# SCH.net
KiCad netlist of a schematic drawn in Altium Designer
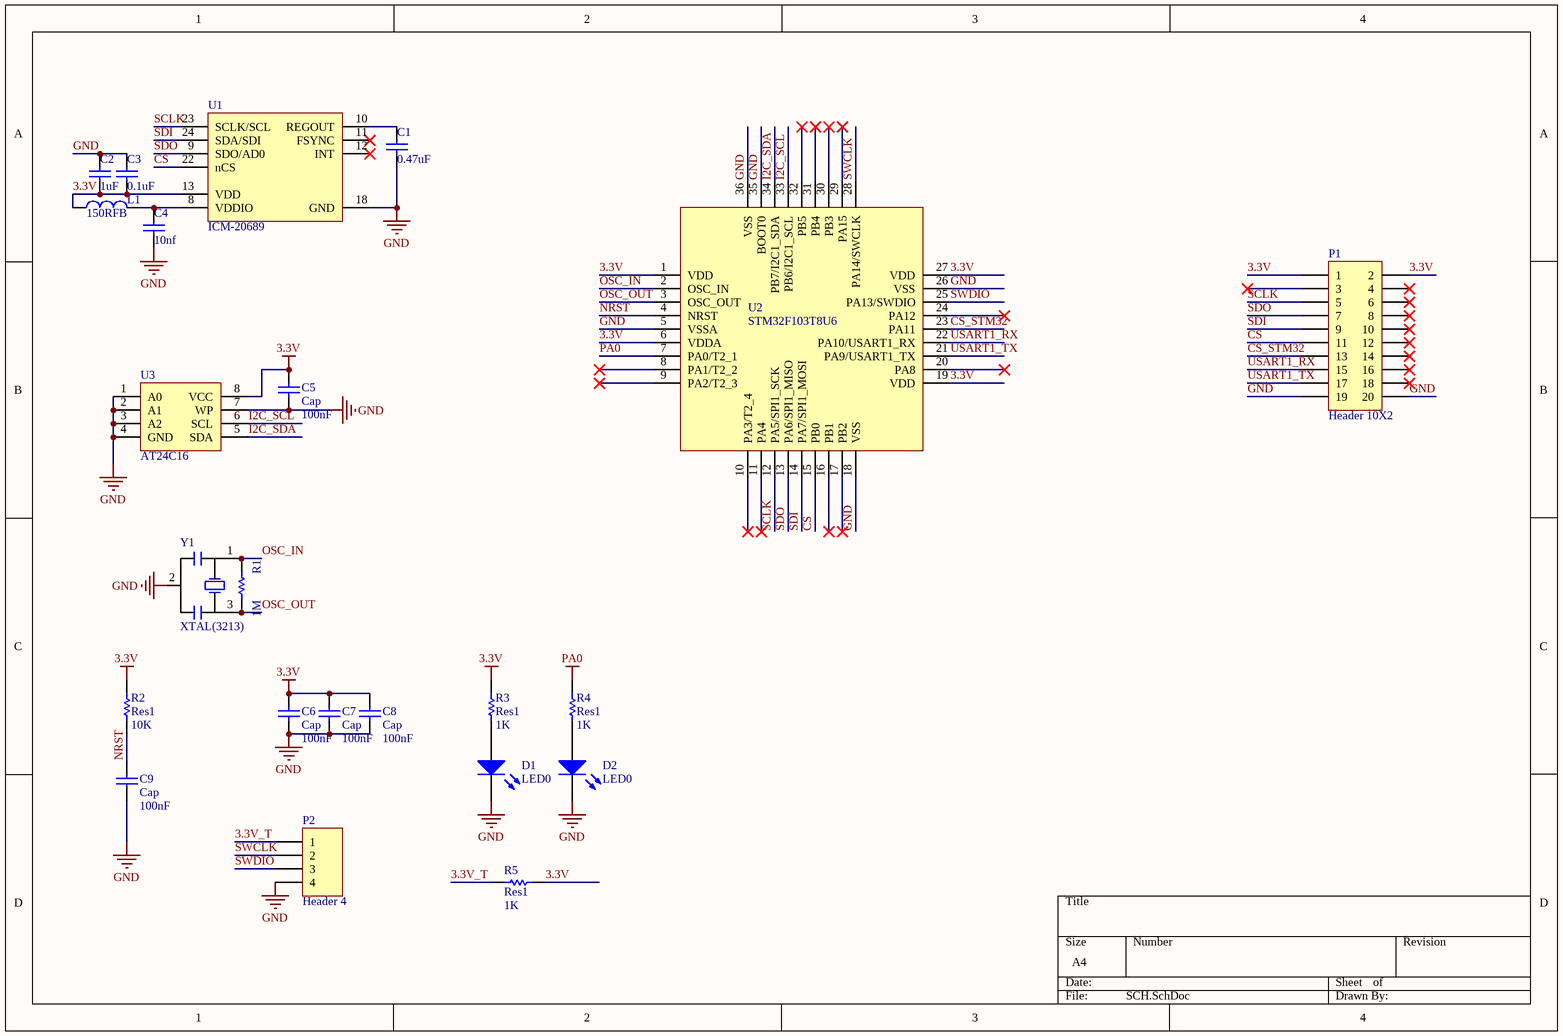
[diagram p0: SCH.SchDoc]

(export (version "E")
  (design (tool "Eeschema 10.0.6"))
  (components
    (comp (ref "C1")
      (value "0.47uF")
      (footprint "c0603")
      (description "Capacitor")
      (fields (field (name "Comment") "Cap") (field (name "PUBLISHER") "Altium Limited"))
      (libsource (lib "Miscellaneous Devices") (part "Cap"))
    )
    (comp (ref "C2")
      (value "1uF")
      (footprint "c0603")
      (description "Capacitor")
      (fields (field (name "Comment") "Cap") (field (name "PUBLISHER") "Altium Limited"))
      (libsource (lib "Miscellaneous Devices") (part "Cap"))
    )
    (comp (ref "C3")
      (value "0.1uF")
      (footprint "c0603")
      (description "Capacitor")
      (fields (field (name "Comment") "Cap") (field (name "PUBLISHER") "Altium Limited"))
      (libsource (lib "Miscellaneous Devices") (part "Cap"))
    )
    (comp (ref "C4")
      (value "10nf")
      (footprint "c0603")
      (description "Capacitor")
      (fields (field (name "Comment") "Cap") (field (name "PUBLISHER") "Altium Limited"))
      (libsource (lib "Miscellaneous Devices") (part "Cap"))
    )
    (comp (ref "C5")
      (value "Cap")
      (footprint "C0603")
      (description "Capacitor")
      (fields (field (name "ALTIUM_VALUE") "100nF") (field (name "PUBLISHER") "Altium Limited"))
      (libsource (lib "Miscellaneous Devices") (part "Cap"))
    )
    (comp (ref "C6")
      (value "Cap")
      (footprint "C0603")
      (description "Capacitor")
      (fields (field (name "ALTIUM_VALUE") "100nF") (field (name "PUBLISHER") "Altium Limited"))
      (libsource (lib "Miscellaneous Devices") (part "Cap"))
    )
    (comp (ref "C7")
      (value "Cap")
      (footprint "C0603")
      (description "Capacitor")
      (fields (field (name "ALTIUM_VALUE") "100nF") (field (name "PUBLISHER") "Altium Limited"))
      (libsource (lib "Miscellaneous Devices") (part "Cap"))
    )
    (comp (ref "C8")
      (value "Cap")
      (footprint "C0603")
      (description "Capacitor")
      (fields (field (name "ALTIUM_VALUE") "100nF") (field (name "PUBLISHER") "Altium Limited"))
      (libsource (lib "Miscellaneous Devices") (part "Cap"))
    )
    (comp (ref "C9")
      (value "Cap")
      (footprint "C0603")
      (description "Capacitor")
      (fields (field (name "ALTIUM_VALUE") "100nF") (field (name "PUBLISHER") "Altium Limited"))
      (libsource (lib "Miscellaneous Devices") (part "Cap"))
    )
    (comp (ref "D1")
      (value "LED0")
      (footprint "0603D")
      (description "Typical INFRARED GaAs LED")
      (fields (field (name "PUBLISHER") "Altium Limited"))
      (libsource (lib "Miscellaneous Devices") (part "LED0"))
    )
    (comp (ref "D2")
      (value "LED0")
      (footprint "0603D")
      (description "Typical INFRARED GaAs LED")
      (fields (field (name "PUBLISHER") "Altium Limited"))
      (libsource (lib "Miscellaneous Devices") (part "LED0"))
    )
    (comp (ref "L1")
      (value "150RFB")
      (footprint "r0603")
      (fields (field (name "Comment") "Inductors"))
      (libsource (lib "schlib_by_wjy") (part "Inductors"))
    )
    (comp (ref "P1")
      (value "Header 10X2")
      (footprint "0.5_2x10P")
      (description "Header, 10-Pin, Dual row")
      (fields (field (name "PUBLISHER") "Altium Limited"))
      (libsource (lib "Miscellaneous Connectors") (part "Header 10X2"))
    )
    (comp (ref "P2")
      (value "Header 4")
      (footprint "1.0*4PIN/SMD H")
      (description "Header, 4-Pin")
      (fields (field (name "PUBLISHER") "Altium Limited"))
      (libsource (lib "Miscellaneous Connectors") (part "Header 4"))
    )
    (comp (ref "R1")
      (value "1M")
      (footprint "R0603")
      (description "Resistor")
      (fields (field (name "Comment") "Res1") (field (name "PUBLISHER") "Altium Limited"))
      (libsource (lib "Miscellaneous Devices") (part "Res1"))
    )
    (comp (ref "R2")
      (value "Res1")
      (footprint "R0603")
      (description "Resistor")
      (fields (field (name "ALTIUM_VALUE") "10K") (field (name "PUBLISHER") "Altium Limited"))
      (libsource (lib "Miscellaneous Devices") (part "Res1"))
    )
    (comp (ref "R3")
      (value "Res1")
      (footprint "R0603")
      (description "Resistor")
      (fields (field (name "ALTIUM_VALUE") "1K") (field (name "PUBLISHER") "Altium Limited"))
      (libsource (lib "Miscellaneous Devices") (part "Res1"))
    )
    (comp (ref "R4")
      (value "Res1")
      (footprint "R0603")
      (description "Resistor")
      (fields (field (name "ALTIUM_VALUE") "1K") (field (name "PUBLISHER") "Altium Limited"))
      (libsource (lib "Miscellaneous Devices") (part "Res1"))
    )
    (comp (ref "R5")
      (value "Res1")
      (footprint "R0603")
      (description "Resistor")
      (fields (field (name "ALTIUM_VALUE") "1K") (field (name "PUBLISHER") "Altium Limited"))
      (libsource (lib "Miscellaneous Devices") (part "Res1"))
    )
    (comp (ref "U1")
      (value "ICM-20689")
      (footprint "QFN24")
      (libsource (lib "schlib_by_wjy") (part "ICM-20689"))
    )
    (comp (ref "U2")
      (value "STM32F103T8U6")
      (footprint "VFQFPN36")
      (libsource (lib "四旋翼") (part "STM32F103T8U6"))
    )
    (comp (ref "U3") (value "AT24C16") (footprint "TSSOP8") (libsource (lib "四旋翼") (part "AT24C16")))
    (comp (ref "Y1")
      (value "XTAL(3213)")
      (footprint "Y3213")
      (description "Crystal Oscillator")
      (fields (field (name "PUBLISHER") "Altium Limited"))
      (libsource (lib "四旋翼") (part "XTAL(3213)"))
    )
  )
  (nets
    (net (code "1") (name "/3.3V_T") (class "Default")
      (node (ref "P2") (pin "1") (pinfunction "1_1") (pintype "passive"))
      (node (ref "R5") (pin "2") (pinfunction "2_2") (pintype "passive"))
    )
    (net (code "2") (name "/CS") (class "Default")
      (node (ref "P1") (pin "11") (pinfunction "11_11") (pintype "passive"))
      (node (ref "U1") (pin "22") (pinfunction "nCS_22") (pintype "passive"))
      (node (ref "U2") (pin "15") (pinfunction "PB0_15") (pintype "passive"))
    )
    (net (code "3") (name "/CS_STM32") (class "Default")
      (node (ref "P1") (pin "13") (pinfunction "13_13") (pintype "passive"))
      (node (ref "U2") (pin "23") (pinfunction "PA11_23") (pintype "passive"))
    )
    (net (code "4") (name "/I2C_SCL") (class "Default")
      (node (ref "U2") (pin "33") (pinfunction "PB6/I2C1_SCL_33") (pintype "passive"))
      (node (ref "U3") (pin "6") (pinfunction "SCL_6") (pintype "passive"))
    )
    (net (code "5") (name "/I2C_SDA") (class "Default")
      (node (ref "U2") (pin "34") (pinfunction "PB7/I2C1_SDA_34") (pintype "passive"))
      (node (ref "U3") (pin "5") (pinfunction "SDA_5") (pintype "passive"))
    )
    (net (code "6") (name "/NRST") (class "Default")
      (node (ref "C9") (pin "2") (pinfunction "2_2") (pintype "passive"))
      (node (ref "R2") (pin "1") (pinfunction "1_1") (pintype "passive"))
      (node (ref "U2") (pin "4") (pinfunction "NRST_4") (pintype "passive"))
    )
    (net (code "7") (name "/OSC_IN") (class "Default")
      (node (ref "R1") (pin "2") (pinfunction "2_2") (pintype "passive"))
      (node (ref "U2") (pin "2") (pinfunction "OSC_IN_2") (pintype "passive"))
      (node (ref "Y1") (pin "1") (pinfunction "OSC1_1") (pintype "passive"))
    )
    (net (code "8") (name "/OSC_OUT") (class "Default")
      (node (ref "R1") (pin "1") (pinfunction "1_1") (pintype "passive"))
      (node (ref "U2") (pin "3") (pinfunction "OSC_OUT_3") (pintype "passive"))
      (node (ref "Y1") (pin "3") (pinfunction "OSC2_3") (pintype "passive"))
    )
    (net (code "9") (name "/SCLK") (class "Default")
      (node (ref "P1") (pin "5") (pinfunction "5_5") (pintype "passive"))
      (node (ref "U1") (pin "23") (pinfunction "SCLK/SCL_23") (pintype "passive"))
      (node (ref "U2") (pin "12") (pinfunction "PA5/SPI1_SCK_12") (pintype "passive"))
    )
    (net (code "10") (name "/SDI") (class "Default")
      (node (ref "P1") (pin "9") (pinfunction "9_9") (pintype "passive"))
      (node (ref "U1") (pin "24") (pinfunction "SDA/SDI_24") (pintype "passive"))
      (node (ref "U2") (pin "14") (pinfunction "PA7/SPI1_MOSI_14") (pintype "passive"))
    )
    (net (code "11") (name "/SDO") (class "Default")
      (node (ref "P1") (pin "7") (pinfunction "7_7") (pintype "passive"))
      (node (ref "U1") (pin "9") (pinfunction "SDO/AD0_9") (pintype "passive"))
      (node (ref "U2") (pin "13") (pinfunction "PA6/SPI1_MISO_13") (pintype "passive"))
    )
    (net (code "12") (name "/SWCLK") (class "Default")
      (node (ref "P2") (pin "2") (pinfunction "2_2") (pintype "passive"))
      (node (ref "U2") (pin "28") (pinfunction "PA14/SWCLK_28") (pintype "passive"))
    )
    (net (code "13") (name "/SWDIO") (class "Default")
      (node (ref "P2") (pin "3") (pinfunction "3_3") (pintype "passive"))
      (node (ref "U2") (pin "25") (pinfunction "PA13/SWDIO_25") (pintype "passive"))
    )
    (net (code "14") (name "/USART1_RX") (class "Default")
      (node (ref "P1") (pin "15") (pinfunction "15_15") (pintype "passive"))
      (node (ref "U2") (pin "22") (pinfunction "PA10/USART1_RX_22") (pintype "passive"))
    )
    (net (code "15") (name "/USART1_TX") (class "Default")
      (node (ref "P1") (pin "17") (pinfunction "17_17") (pintype "passive"))
      (node (ref "U2") (pin "21") (pinfunction "PA9/USART1_TX_21") (pintype "passive"))
    )
    (net (code "16") (name "3.3V") (class "Default")
      (node (ref "C2") (pin "1") (pinfunction "1_1") (pintype "passive"))
      (node (ref "C3") (pin "1") (pinfunction "1_1") (pintype "passive"))
      (node (ref "C5") (pin "2") (pinfunction "2_2") (pintype "passive"))
      (node (ref "C6") (pin "2") (pinfunction "2_2") (pintype "passive"))
      (node (ref "C7") (pin "2") (pinfunction "2_2") (pintype "passive"))
      (node (ref "C8") (pin "2") (pinfunction "2_2") (pintype "passive"))
      (node (ref "L1") (pin "1") (pinfunction "1_1") (pintype "passive"))
      (node (ref "P1") (pin "1") (pinfunction "1_1") (pintype "passive"))
      (node (ref "P1") (pin "2") (pinfunction "2_2") (pintype "passive"))
      (node (ref "R2") (pin "2") (pinfunction "2_2") (pintype "passive"))
      (node (ref "R3") (pin "2") (pinfunction "2_2") (pintype "passive"))
      (node (ref "R5") (pin "1") (pinfunction "1_1") (pintype "passive"))
      (node (ref "U1") (pin "13") (pinfunction "VDD_13") (pintype "passive"))
      (node (ref "U2") (pin "1") (pinfunction "VDD_1") (pintype "passive"))
      (node (ref "U2") (pin "19") (pinfunction "VDD_19") (pintype "passive"))
      (node (ref "U2") (pin "27") (pinfunction "VDD_27") (pintype "passive"))
      (node (ref "U2") (pin "6") (pinfunction "VDDA_6") (pintype "passive"))
      (node (ref "U3") (pin "8") (pinfunction "VCC_8") (pintype "passive"))
    )
    (net (code "17") (name "GND") (class "Default")
      (node (ref "C1") (pin "1") (pinfunction "1_1") (pintype "passive"))
      (node (ref "C2") (pin "2") (pinfunction "2_2") (pintype "passive"))
      (node (ref "C3") (pin "2") (pinfunction "2_2") (pintype "passive"))
      (node (ref "C4") (pin "1") (pinfunction "1_1") (pintype "passive"))
      (node (ref "C5") (pin "1") (pinfunction "1_1") (pintype "passive"))
      (node (ref "C6") (pin "1") (pinfunction "1_1") (pintype "passive"))
      (node (ref "C7") (pin "1") (pinfunction "1_1") (pintype "passive"))
      (node (ref "C8") (pin "1") (pinfunction "1_1") (pintype "passive"))
      (node (ref "C9") (pin "1") (pinfunction "1_1") (pintype "passive"))
      (node (ref "D1") (pin "2") (pinfunction "K_2") (pintype "passive"))
      (node (ref "D2") (pin "2") (pinfunction "K_2") (pintype "passive"))
      (node (ref "P1") (pin "19") (pinfunction "19_19") (pintype "passive"))
      (node (ref "P1") (pin "20") (pinfunction "20_20") (pintype "passive"))
      (node (ref "P2") (pin "4") (pinfunction "4_4") (pintype "passive"))
      (node (ref "U1") (pin "18") (pinfunction "GND_18") (pintype "passive"))
      (node (ref "U2") (pin "18") (pinfunction "VSS_18") (pintype "passive"))
      (node (ref "U2") (pin "26") (pinfunction "VSS_26") (pintype "passive"))
      (node (ref "U2") (pin "35") (pinfunction "BOOT0_35") (pintype "passive"))
      (node (ref "U2") (pin "36") (pinfunction "VSS_36") (pintype "passive"))
      (node (ref "U2") (pin "5") (pinfunction "VSSA_5") (pintype "passive"))
      (node (ref "U3") (pin "1") (pinfunction "A0_1") (pintype "passive"))
      (node (ref "U3") (pin "2") (pinfunction "A1_2") (pintype "passive"))
      (node (ref "U3") (pin "3") (pinfunction "A2_3") (pintype "passive"))
      (node (ref "U3") (pin "4") (pinfunction "GND_4") (pintype "passive"))
      (node (ref "U3") (pin "7") (pinfunction "WP_7") (pintype "passive"))
      (node (ref "Y1") (pin "2") (pinfunction "GND_2") (pintype "passive"))
    )
    (net (code "18") (name "Net-(D1-A)") (class "Default")
      (node (ref "D1") (pin "1") (pinfunction "A_1") (pintype "passive"))
      (node (ref "R3") (pin "1") (pinfunction "1_1") (pintype "passive"))
    )
    (net (code "19") (name "Net-(D2-A)") (class "Default")
      (node (ref "D2") (pin "1") (pinfunction "A_1") (pintype "passive"))
      (node (ref "R4") (pin "1") (pinfunction "1_1") (pintype "passive"))
    )
    (net (code "20") (name "Net-(U1-REGOUT)") (class "Default")
      (node (ref "C1") (pin "2") (pinfunction "2_2") (pintype "passive"))
      (node (ref "U1") (pin "10") (pinfunction "REGOUT_10") (pintype "passive"))
    )
    (net (code "21") (name "Net-(U1-VDDIO)") (class "Default")
      (node (ref "C4") (pin "2") (pinfunction "2_2") (pintype "passive"))
      (node (ref "L1") (pin "2") (pinfunction "2_2") (pintype "passive"))
      (node (ref "U1") (pin "8") (pinfunction "VDDIO_8") (pintype "passive"))
    )
    (net (code "22") (name "PA0") (class "Default")
      (node (ref "R4") (pin "2") (pinfunction "2_2") (pintype "passive"))
      (node (ref "U2") (pin "7") (pinfunction "PA0/T2_1_7") (pintype "passive"))
    )
    (net (code "23") (name "unconnected-(P1-Pad3)") (class "Default")
      (node (ref "P1") (pin "3") (pinfunction "3_3") (pintype "passive+no_connect"))
    )
    (net (code "24") (name "unconnected-(P1-Pad4)") (class "Default")
      (node (ref "P1") (pin "4") (pinfunction "4_4") (pintype "passive+no_connect"))
    )
    (net (code "25") (name "unconnected-(P1-Pad6)") (class "Default")
      (node (ref "P1") (pin "6") (pinfunction "6_6") (pintype "passive+no_connect"))
    )
    (net (code "26") (name "unconnected-(P1-Pad8)") (class "Default")
      (node (ref "P1") (pin "8") (pinfunction "8_8") (pintype "passive+no_connect"))
    )
    (net (code "27") (name "unconnected-(P1-Pad10)") (class "Default")
      (node (ref "P1") (pin "10") (pinfunction "10_10") (pintype "passive+no_connect"))
    )
    (net (code "28") (name "unconnected-(P1-Pad12)") (class "Default")
      (node (ref "P1") (pin "12") (pinfunction "12_12") (pintype "passive+no_connect"))
    )
    (net (code "29") (name "unconnected-(P1-Pad14)") (class "Default")
      (node (ref "P1") (pin "14") (pinfunction "14_14") (pintype "passive+no_connect"))
    )
    (net (code "30") (name "unconnected-(P1-Pad16)") (class "Default")
      (node (ref "P1") (pin "16") (pinfunction "16_16") (pintype "passive+no_connect"))
    )
    (net (code "31") (name "unconnected-(P1-Pad18)") (class "Default")
      (node (ref "P1") (pin "18") (pinfunction "18_18") (pintype "passive+no_connect"))
    )
    (net (code "32") (name "unconnected-(U1-FSYNC-Pad11)") (class "Default")
      (node (ref "U1") (pin "11") (pinfunction "FSYNC_11") (pintype "passive+no_connect"))
    )
    (net (code "33") (name "unconnected-(U1-INT-Pad12)") (class "Default")
      (node (ref "U1") (pin "12") (pinfunction "INT_12") (pintype "passive+no_connect"))
    )
    (net (code "34") (name "unconnected-(U2-PA1{slash}T2_2-Pad8)") (class "Default")
      (node (ref "U2") (pin "8") (pinfunction "PA1/T2_2_8") (pintype "passive+no_connect"))
    )
    (net (code "35") (name "unconnected-(U2-PA2{slash}T2_3-Pad9)") (class "Default")
      (node (ref "U2") (pin "9") (pinfunction "PA2/T2_3_9") (pintype "passive+no_connect"))
    )
    (net (code "36") (name "unconnected-(U2-PA3{slash}T2_4-Pad10)") (class "Default")
      (node (ref "U2") (pin "10") (pinfunction "PA3/T2_4_10") (pintype "passive+no_connect"))
    )
    (net (code "37") (name "unconnected-(U2-PA4-Pad11)") (class "Default")
      (node (ref "U2") (pin "11") (pinfunction "PA4_11") (pintype "passive+no_connect"))
    )
    (net (code "38") (name "unconnected-(U2-PA8-Pad20)") (class "Default")
      (node (ref "U2") (pin "20") (pinfunction "PA8_20") (pintype "passive+no_connect"))
    )
    (net (code "39") (name "unconnected-(U2-PA12-Pad24)") (class "Default")
      (node (ref "U2") (pin "24") (pinfunction "PA12_24") (pintype "passive+no_connect"))
    )
    (net (code "40") (name "unconnected-(U2-PA15-Pad29)") (class "Default")
      (node (ref "U2") (pin "29") (pinfunction "PA15_29") (pintype "passive+no_connect"))
    )
    (net (code "41") (name "unconnected-(U2-PB1-Pad16)") (class "Default")
      (node (ref "U2") (pin "16") (pinfunction "PB1_16") (pintype "passive+no_connect"))
    )
    (net (code "42") (name "unconnected-(U2-PB2-Pad17)") (class "Default")
      (node (ref "U2") (pin "17") (pinfunction "PB2_17") (pintype "passive+no_connect"))
    )
    (net (code "43") (name "unconnected-(U2-PB3-Pad30)") (class "Default")
      (node (ref "U2") (pin "30") (pinfunction "PB3_30") (pintype "passive+no_connect"))
    )
    (net (code "44") (name "unconnected-(U2-PB4-Pad31)") (class "Default")
      (node (ref "U2") (pin "31") (pinfunction "PB4_31") (pintype "passive+no_connect"))
    )
    (net (code "45") (name "unconnected-(U2-PB5-Pad32)") (class "Default")
      (node (ref "U2") (pin "32") (pinfunction "PB5_32") (pintype "passive+no_connect"))
    )
  )
)
